# MCU.net
KiCad netlist of a schematic drawn in Altium Designer
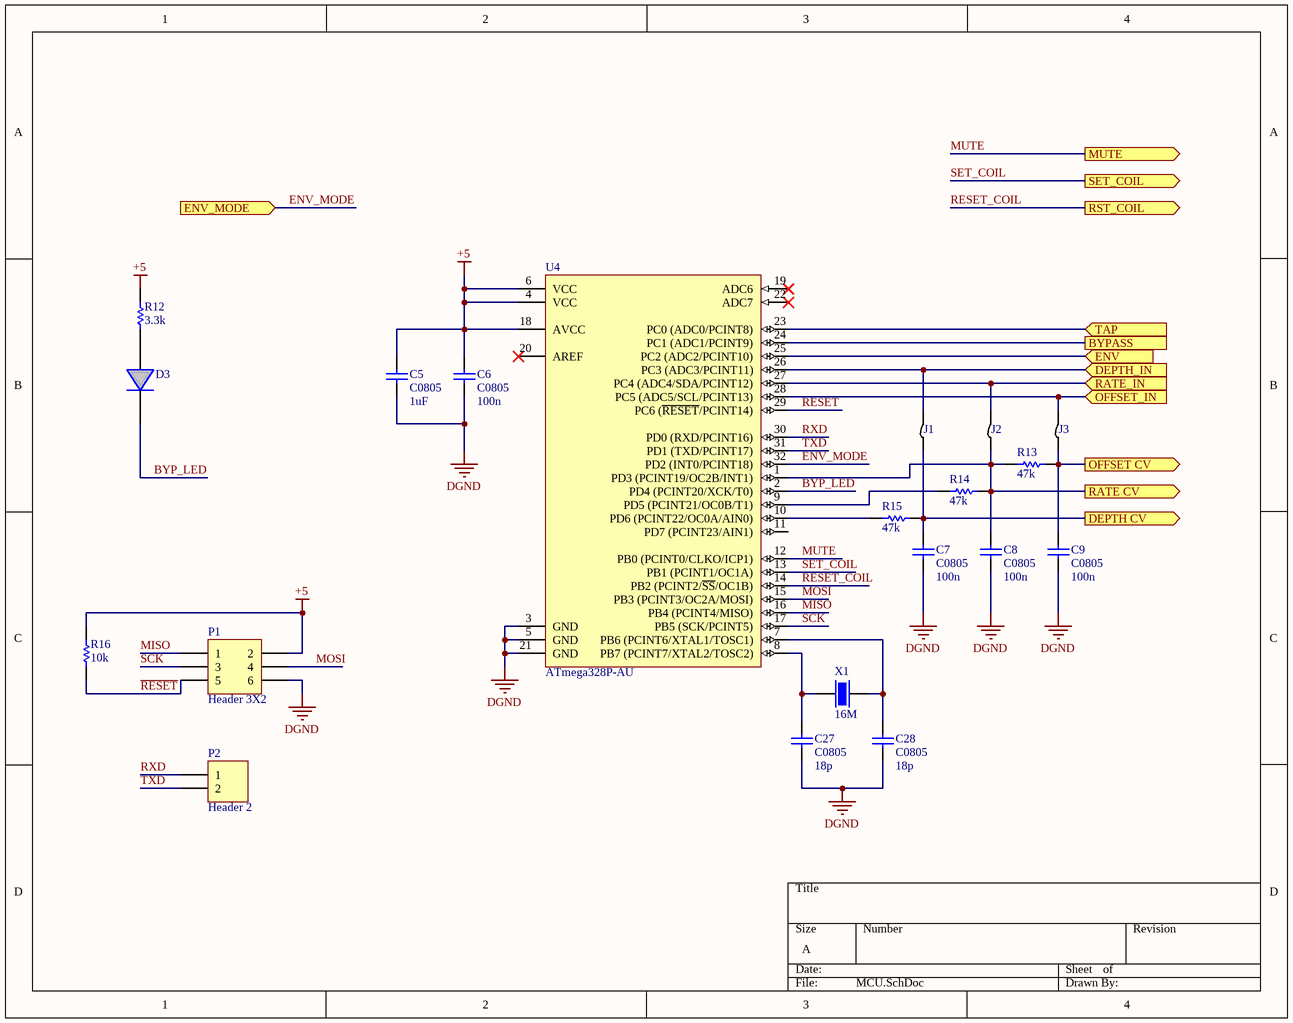
[diagram p0: MCU.SchDoc]

(export (version "E")
  (design (tool "Eeschema 10.0.6"))
  (components
    (comp (ref "C5")
      (value "C0805")
      (footprint "0805")
      (description "Ceramic Chip Capacitor - Standard")
      (fields (field (name "ALTIUM_VALUE") "1uF") (field (name "PUBLISHER") "Altium Limited"))
      (libsource (lib "KEMET Chip Capacitor") (part "C0805"))
    )
    (comp (ref "C6")
      (value "C0805")
      (footprint "0805")
      (description "Ceramic Chip Capacitor - Standard")
      (fields (field (name "ALTIUM_VALUE") "100n") (field (name "PUBLISHER") "Altium Limited"))
      (libsource (lib "KEMET Chip Capacitor") (part "C0805"))
    )
    (comp (ref "C7")
      (value "C0805")
      (footprint "0805")
      (description "Ceramic Chip Capacitor - Standard")
      (fields (field (name "ALTIUM_VALUE") "100n") (field (name "PUBLISHER") "Altium Limited"))
      (libsource (lib "KEMET Chip Capacitor") (part "C0805"))
    )
    (comp (ref "C8")
      (value "C0805")
      (footprint "0805")
      (description "Ceramic Chip Capacitor - Standard")
      (fields (field (name "ALTIUM_VALUE") "100n") (field (name "PUBLISHER") "Altium Limited"))
      (libsource (lib "KEMET Chip Capacitor") (part "C0805"))
    )
    (comp (ref "C9")
      (value "C0805")
      (footprint "0805")
      (description "Ceramic Chip Capacitor - Standard")
      (fields (field (name "ALTIUM_VALUE") "100n") (field (name "PUBLISHER") "Altium Limited"))
      (libsource (lib "KEMET Chip Capacitor") (part "C0805"))
    )
    (comp (ref "C27")
      (value "C0805")
      (footprint "0805")
      (description "Ceramic Chip Capacitor - Standard")
      (fields (field (name "ALTIUM_VALUE") "18p") (field (name "PUBLISHER") "Altium Limited"))
      (libsource (lib "KEMET Chip Capacitor") (part "C0805"))
    )
    (comp (ref "C28")
      (value "C0805")
      (footprint "0805")
      (description "Ceramic Chip Capacitor - Standard")
      (fields (field (name "ALTIUM_VALUE") "18p") (field (name "PUBLISHER") "Altium Limited"))
      (libsource (lib "KEMET Chip Capacitor") (part "C0805"))
    )
    (comp (ref "D3") (value "LED5MM") (footprint "LED5MM") (libsource (lib "Parts") (part "LED5MM")))
    (comp (ref "J1") (value "Jumper") (footprint "Jumper") (libsource (lib "Parts") (part "Jumper")))
    (comp (ref "J2") (value "Jumper") (footprint "Jumper") (libsource (lib "Parts") (part "Jumper")))
    (comp (ref "J3") (value "Jumper") (footprint "Jumper") (libsource (lib "Parts") (part "Jumper")))
    (comp (ref "P1")
      (value "Header 3X2")
      (footprint "HDR2X3")
      (description "Header, 3-Pin, Dual row")
      (fields (field (name "PUBLISHER") "Altium Limited"))
      (libsource (lib "Miscellaneous Connectors") (part "Header 3X2"))
    )
    (comp (ref "P2")
      (value "Header 2")
      (footprint "HDR1X2")
      (description "Header, 2-Pin")
      (fields (field (name "PUBLISHER") "Altium Limited"))
      (libsource (lib "Miscellaneous Connectors") (part "Header 2"))
    )
    (comp (ref "R12")
      (value "3.3k")
      (footprint "ERA-0805")
      (description "Resistor 0805")
      (fields (field (name "PUBLISHER") "Altium Limited"))
      (libsource (lib "Panasonic Resistor") (part "ERAS"))
    )
    (comp (ref "R13")
      (value "47k")
      (footprint "ERA-0805")
      (description "Resistor 0805")
      (fields (field (name "PUBLISHER") "Altium Limited"))
      (libsource (lib "Panasonic Resistor") (part "ERAS"))
    )
    (comp (ref "R14")
      (value "47k")
      (footprint "ERA-0805")
      (description "Resistor 0805")
      (fields (field (name "PUBLISHER") "Altium Limited"))
      (libsource (lib "Panasonic Resistor") (part "ERAS"))
    )
    (comp (ref "R15")
      (value "47k")
      (footprint "ERA-0805")
      (description "Resistor 0805")
      (fields (field (name "PUBLISHER") "Altium Limited"))
      (libsource (lib "Panasonic Resistor") (part "ERAS"))
    )
    (comp (ref "R16")
      (value "10k")
      (footprint "ERA-0805")
      (description "Resistor 0805")
      (fields (field (name "PUBLISHER") "Altium Limited"))
      (libsource (lib "Panasonic Resistor") (part "ERAS"))
    )
    (comp (ref "U4")
      (value "ATmega328P-AU")
      (footprint "32A_N")
      (fields (field (name "PUBLISHER") "Altium Limited"))
      (libsource (lib "Atmel Microcontroller 8-Bit megaAVR") (part "ATmega328P-AU"))
    )
    (comp (ref "X1")
      (value "16M")
      (footprint "XTAL PTH")
      (fields (field (name "MPN") "ECS-160-20-4X"))
      (libsource (lib "Parts") (part "Crystal PTH"))
    )
  )
  (nets
    (net (code "1") (name "+5") (class "Default")
      (node (ref "C5") (pin "2") (pinfunction "2_2") (pintype "passive"))
      (node (ref "C6") (pin "2") (pinfunction "2_2") (pintype "passive"))
      (node (ref "P1") (pin "2") (pinfunction "2_2") (pintype "passive"))
      (node (ref "R12") (pin "2") (pinfunction "2_2") (pintype "passive"))
      (node (ref "R16") (pin "2") (pinfunction "2_2") (pintype "passive"))
      (node (ref "U4") (pin "18") (pinfunction "AVCC_18") (pintype "power_in"))
      (node (ref "U4") (pin "4") (pinfunction "VCC_4") (pintype "power_in"))
      (node (ref "U4") (pin "6") (pinfunction "VCC_6") (pintype "power_in"))
    )
    (net (code "2") (name "/BYPASS") (class "Default")
      (node (ref "U4") (pin "24") (pinfunction "PC1_(ADC1/PCINT9)_24") (pintype "bidirectional"))
    )
    (net (code "3") (name "/BYP_LED") (class "Default")
      (node (ref "D3") (pin "1") (pinfunction "1_1") (pintype "passive"))
      (node (ref "U4") (pin "2") (pinfunction "PD4_(PCINT20/XCK/T0)_2") (pintype "bidirectional"))
    )
    (net (code "4") (name "/DEPTH CV") (class "Default")
      (node (ref "C7") (pin "2") (pinfunction "2_2") (pintype "passive"))
      (node (ref "J1") (pin "1") (pinfunction "1_1") (pintype "passive"))
      (node (ref "R15") (pin "2") (pinfunction "2_2") (pintype "passive"))
    )
    (net (code "5") (name "/DEPTH_IN") (class "Default")
      (node (ref "J1") (pin "2") (pinfunction "2_2") (pintype "passive"))
      (node (ref "U4") (pin "26") (pinfunction "PC3_(ADC3/PCINT11)_26") (pintype "bidirectional"))
    )
    (net (code "6") (name "/ENV") (class "Default")
      (node (ref "U4") (pin "25") (pinfunction "PC2_(ADC2/PCINT10)_25") (pintype "bidirectional"))
    )
    (net (code "7") (name "/ENV_MODE") (class "Default")
      (node (ref "U4") (pin "32") (pinfunction "PD2_(INT0/PCINT18)_32") (pintype "bidirectional"))
    )
    (net (code "8") (name "/MISO") (class "Default")
      (node (ref "P1") (pin "1") (pinfunction "1_1") (pintype "passive"))
      (node (ref "U4") (pin "16") (pinfunction "PB4_(PCINT4/MISO)_16") (pintype "bidirectional"))
    )
    (net (code "9") (name "/MOSI") (class "Default")
      (node (ref "P1") (pin "4") (pinfunction "4_4") (pintype "passive"))
      (node (ref "U4") (pin "15") (pinfunction "PB3_(PCINT3/OC2A/MOSI)_15") (pintype "bidirectional"))
    )
    (net (code "10") (name "/MUTE") (class "Default")
      (node (ref "U4") (pin "12") (pinfunction "PB0_(PCINT0/CLKO/ICP1)_12") (pintype "bidirectional"))
    )
    (net (code "11") (name "/OFFSET CV") (class "Default")
      (node (ref "C9") (pin "2") (pinfunction "2_2") (pintype "passive"))
      (node (ref "J3") (pin "1") (pinfunction "1_1") (pintype "passive"))
      (node (ref "R13") (pin "2") (pinfunction "2_2") (pintype "passive"))
    )
    (net (code "12") (name "/OFFSET_IN") (class "Default")
      (node (ref "J3") (pin "2") (pinfunction "2_2") (pintype "passive"))
      (node (ref "U4") (pin "28") (pinfunction "PC5_(ADC5/SCL/PCINT13)_28") (pintype "bidirectional"))
    )
    (net (code "13") (name "/RATE CV") (class "Default")
      (node (ref "C8") (pin "2") (pinfunction "2_2") (pintype "passive"))
      (node (ref "J2") (pin "1") (pinfunction "1_1") (pintype "passive"))
      (node (ref "R13") (pin "1") (pinfunction "1_1") (pintype "passive"))
      (node (ref "R14") (pin "2") (pinfunction "2_2") (pintype "passive"))
      (node (ref "U4") (pin "1") (pinfunction "PD3_(PCINT19/OC2B/INT1)_1") (pintype "bidirectional"))
    )
    (net (code "14") (name "/RATE_IN") (class "Default")
      (node (ref "J2") (pin "2") (pinfunction "2_2") (pintype "passive"))
      (node (ref "U4") (pin "27") (pinfunction "PC4_(ADC4/SDA/PCINT12)_27") (pintype "bidirectional"))
    )
    (net (code "15") (name "/RESET_COIL") (class "Default")
      (node (ref "U4") (pin "14") (pinfunction "PB2_(PCINT2/~{SS}/OC1B)_14") (pintype "bidirectional"))
    )
    (net (code "16") (name "/RXD") (class "Default")
      (node (ref "P2") (pin "1") (pinfunction "1_1") (pintype "passive"))
      (node (ref "U4") (pin "30") (pinfunction "PD0_(RXD/PCINT16)_30") (pintype "bidirectional"))
    )
    (net (code "17") (name "/SCK") (class "Default")
      (node (ref "P1") (pin "3") (pinfunction "3_3") (pintype "passive"))
      (node (ref "U4") (pin "17") (pinfunction "PB5_(SCK/PCINT5)_17") (pintype "bidirectional"))
    )
    (net (code "18") (name "/SET_COIL") (class "Default")
      (node (ref "U4") (pin "13") (pinfunction "PB1_(PCINT1/OC1A)_13") (pintype "bidirectional"))
    )
    (net (code "19") (name "/TAP") (class "Default")
      (node (ref "U4") (pin "23") (pinfunction "PC0_(ADC0/PCINT8)_23") (pintype "bidirectional"))
    )
    (net (code "20") (name "/TXD") (class "Default")
      (node (ref "P2") (pin "2") (pinfunction "2_2") (pintype "passive"))
      (node (ref "U4") (pin "31") (pinfunction "PD1_(TXD/PCINT17)_31") (pintype "bidirectional"))
    )
    (net (code "21") (name "/~{RESET}") (class "Default")
      (node (ref "P1") (pin "5") (pinfunction "5_5") (pintype "passive"))
      (node (ref "R16") (pin "1") (pinfunction "1_1") (pintype "passive"))
      (node (ref "U4") (pin "29") (pinfunction "PC6_(~{RESET}/PCINT14)_29") (pintype "bidirectional"))
    )
    (net (code "22") (name "DGND") (class "Default")
      (node (ref "C27") (pin "1") (pinfunction "1_1") (pintype "passive"))
      (node (ref "C28") (pin "1") (pinfunction "1_1") (pintype "passive"))
      (node (ref "C5") (pin "1") (pinfunction "1_1") (pintype "passive"))
      (node (ref "C6") (pin "1") (pinfunction "1_1") (pintype "passive"))
      (node (ref "C7") (pin "1") (pinfunction "1_1") (pintype "passive"))
      (node (ref "C8") (pin "1") (pinfunction "1_1") (pintype "passive"))
      (node (ref "C9") (pin "1") (pinfunction "1_1") (pintype "passive"))
      (node (ref "P1") (pin "6") (pinfunction "6_6") (pintype "passive"))
      (node (ref "U4") (pin "21") (pinfunction "GND_21") (pintype "power_in"))
      (node (ref "U4") (pin "3") (pinfunction "GND_3") (pintype "power_in"))
      (node (ref "U4") (pin "5") (pinfunction "GND_5") (pintype "power_in"))
    )
    (net (code "23") (name "Net-(D3-Pad0)") (class "Default")
      (node (ref "D3") (pin "0") (pinfunction "0_0") (pintype "passive"))
      (node (ref "R12") (pin "1") (pinfunction "1_1") (pintype "passive"))
    )
    (net (code "24") (name "Net-(U4-PB6_(PCINT6{slash}XTAL1{slash}TOSC1))") (class "Default")
      (node (ref "C28") (pin "2") (pinfunction "2_2") (pintype "passive"))
      (node (ref "U4") (pin "7") (pinfunction "PB6_(PCINT6/XTAL1/TOSC1)_7") (pintype "bidirectional"))
      (node (ref "X1") (pin "2") (pinfunction "2_2") (pintype "passive"))
    )
    (net (code "25") (name "Net-(U4-PB7_(PCINT7{slash}XTAL2{slash}TOSC2))") (class "Default")
      (node (ref "C27") (pin "2") (pinfunction "2_2") (pintype "passive"))
      (node (ref "U4") (pin "8") (pinfunction "PB7_(PCINT7/XTAL2/TOSC2)_8") (pintype "bidirectional"))
      (node (ref "X1") (pin "1") (pinfunction "1_1") (pintype "passive"))
    )
    (net (code "26") (name "Net-(U4-PD5_(PCINT21{slash}OC0B{slash}T1))") (class "Default")
      (node (ref "R14") (pin "1") (pinfunction "1_1") (pintype "passive"))
      (node (ref "U4") (pin "9") (pinfunction "PD5_(PCINT21/OC0B/T1)_9") (pintype "bidirectional"))
    )
    (net (code "27") (name "Net-(U4-PD6_(PCINT22{slash}OC0A{slash}AIN0))") (class "Default")
      (node (ref "R15") (pin "1") (pinfunction "1_1") (pintype "passive"))
      (node (ref "U4") (pin "10") (pinfunction "PD6_(PCINT22/OC0A/AIN0)_10") (pintype "bidirectional"))
    )
    (net (code "28") (name "unconnected-(U4-ADC6-Pad19)") (class "Default")
      (node (ref "U4") (pin "19") (pinfunction "ADC6_19") (pintype "input+no_connect"))
    )
    (net (code "29") (name "unconnected-(U4-ADC7-Pad22)") (class "Default")
      (node (ref "U4") (pin "22") (pinfunction "ADC7_22") (pintype "input+no_connect"))
    )
    (net (code "30") (name "unconnected-(U4-AREF-Pad20)") (class "Default")
      (node (ref "U4") (pin "20") (pinfunction "AREF_20") (pintype "passive+no_connect"))
    )
    (net (code "31") (name "unconnected-(U4-PD7_(PCINT23{slash}AIN1)-Pad11)") (class "Default")
      (node (ref "U4") (pin "11") (pinfunction "PD7_(PCINT23/AIN1)_11") (pintype "bidirectional"))
    )
  )
)
